# RCAuto.net
KiCad netlist of a schematic drawn in Altium Designer
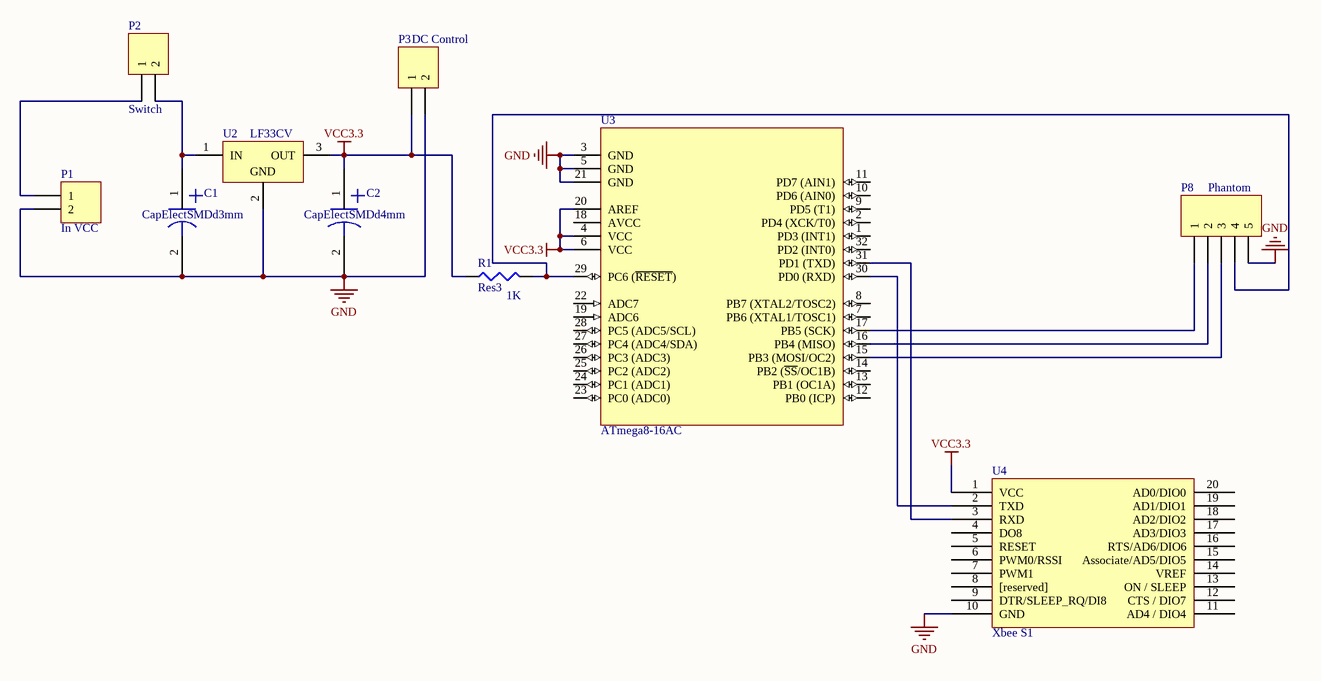
[diagram p0: RCAuto.SchDoc]

(export (version "E")
  (design (tool "Eeschema 10.0.6"))
  (components
    (comp (ref "C1")
      (value "CapElectSMDd3mm")
      (footprint "CapElectSMDd3mm")
      (libsource (lib "CapElectSMDd3mm") (part "CapElectSMDd3mm"))
    )
    (comp (ref "C2")
      (value "CapElectSMDd4mm")
      (footprint "CapElectSMDd4mm")
      (libsource (lib "CapElectSMDd4mm") (part "CapElectSMDd4mm"))
    )
    (comp (ref "P1")
      (value "In VCC")
      (footprint "HDR1X2")
      (description "Header, 2-Pin")
      (fields (field (name "PUBLISHER") "Altium Limited"))
      (libsource (lib "") (part "Header 2_1"))
    )
    (comp (ref "P2")
      (value "Switch")
      (footprint "HDR1X2")
      (description "Header, 2-Pin")
      (fields (field (name "PUBLISHER") "Altium Limited"))
      (libsource (lib "Miscellaneous Connectors") (part "Header 2"))
    )
    (comp (ref "P3")
      (value "DC Control")
      (footprint "HDR1X2")
      (description "Header, 2-Pin")
      (fields (field (name "PUBLISHER") "Altium Limited"))
      (libsource (lib "Miscellaneous Connectors") (part "Header 2"))
    )
    (comp (ref "P8")
      (value "Phantom")
      (footprint "HDR1X5")
      (description "Header, 5-Pin")
      (fields (field (name "PUBLISHER") "Altium Limited"))
      (libsource (lib "Miscellaneous Connectors") (part "Header 5"))
    )
    (comp (ref "R1")
      (value "Res3")
      (footprint "14-1206")
      (description "Resistor")
      (fields (field (name "ALTIUM_VALUE") "1K") (field (name "PUBLISHER") "Altium Limited"))
      (libsource (lib "Miscellaneous Devices") (part "Res3"))
    )
    (comp (ref "U2")
      (value "LF33CV")
      (footprint "TO-220A")
      (description "500mA, Very Low Drop (0.45V) Voltage Regulator")
      (fields (field (name "PUBLISHER") "Altium Limited"))
      (libsource (lib "ST Power Mgt Voltage Regulator") (part "LF33CV"))
    )
    (comp (ref "U3")
      (value "ATmega8-16AC")
      (footprint "32A_N")
      (description "8-Bit AVR Microcontroller with 8K Bytes of In-System Programmable Flash Memory")
      (fields (field (name "PUBLISHER") "Altium Limited"))
      (libsource (lib "Atmel Microcontroller 8-Bit AVR") (part "ATmega8-16AC"))
    )
    (comp (ref "U4") (value "Xbee S1") (footprint "Xbee S1") (libsource (lib "Xbee S1") (part "Xbee S1")))
  )
  (nets
    (net (code "1") (name "GND") (class "Default")
      (node (ref "C1") (pin "2") (pinfunction "2_2") (pintype "passive"))
      (node (ref "C2") (pin "2") (pinfunction "2_2") (pintype "passive"))
      (node (ref "P1") (pin "2") (pinfunction "2_2") (pintype "passive"))
      (node (ref "P3") (pin "2") (pinfunction "2_2") (pintype "passive"))
      (node (ref "P8") (pin "5") (pinfunction "5_5") (pintype "passive"))
      (node (ref "U2") (pin "2") (pinfunction "GND_2") (pintype "power_in"))
      (node (ref "U3") (pin "21") (pinfunction "GND_21") (pintype "power_in"))
      (node (ref "U3") (pin "3") (pinfunction "GND_3") (pintype "power_in"))
      (node (ref "U3") (pin "5") (pinfunction "GND_5") (pintype "power_in"))
      (node (ref "U4") (pin "10") (pinfunction "GND_10") (pintype "passive"))
    )
    (net (code "2") (name "Net-(P1-Pad1)") (class "Default")
      (node (ref "P1") (pin "1") (pinfunction "1_1") (pintype "passive"))
      (node (ref "P2") (pin "1") (pinfunction "1_1") (pintype "passive"))
    )
    (net (code "3") (name "Net-(U2-IN)") (class "Default")
      (node (ref "C1") (pin "1") (pinfunction "1_1") (pintype "passive"))
      (node (ref "P2") (pin "2") (pinfunction "2_2") (pintype "passive"))
      (node (ref "U2") (pin "1") (pinfunction "IN_1") (pintype "power_in"))
    )
    (net (code "4") (name "Net-(U3-PB3_(MOSI{slash}OC2))") (class "Default")
      (node (ref "P8") (pin "3") (pinfunction "3_3") (pintype "passive"))
      (node (ref "U3") (pin "15") (pinfunction "PB3_(MOSI/OC2)_15") (pintype "bidirectional"))
    )
    (net (code "5") (name "Net-(U3-PB4_(MISO))") (class "Default")
      (node (ref "P8") (pin "2") (pinfunction "2_2") (pintype "passive"))
      (node (ref "U3") (pin "16") (pinfunction "PB4_(MISO)_16") (pintype "bidirectional"))
    )
    (net (code "6") (name "Net-(U3-PB5_(SCK))") (class "Default")
      (node (ref "P8") (pin "1") (pinfunction "1_1") (pintype "passive"))
      (node (ref "U3") (pin "17") (pinfunction "PB5_(SCK)_17") (pintype "bidirectional"))
    )
    (net (code "7") (name "Net-(U3-PC6_(~{RESET}))") (class "Default")
      (node (ref "P8") (pin "4") (pinfunction "4_4") (pintype "passive"))
      (node (ref "R1") (pin "2") (pinfunction "2_2") (pintype "passive"))
      (node (ref "U3") (pin "29") (pinfunction "PC6_(~{RESET})_29") (pintype "bidirectional"))
    )
    (net (code "8") (name "Net-(U3-PD0_(RXD))") (class "Default")
      (node (ref "U3") (pin "30") (pinfunction "PD0_(RXD)_30") (pintype "bidirectional"))
      (node (ref "U4") (pin "2") (pinfunction "TXD_2") (pintype "passive"))
    )
    (net (code "9") (name "Net-(U3-PD1_(TXD))") (class "Default")
      (node (ref "U3") (pin "31") (pinfunction "PD1_(TXD)_31") (pintype "bidirectional"))
      (node (ref "U4") (pin "3") (pinfunction "RXD_3") (pintype "passive"))
    )
    (net (code "10") (name "VCC3.3") (class "Default")
      (node (ref "C2") (pin "1") (pinfunction "1_1") (pintype "passive"))
      (node (ref "P3") (pin "1") (pinfunction "1_1") (pintype "passive"))
      (node (ref "R1") (pin "1") (pinfunction "1_1") (pintype "passive"))
      (node (ref "U2") (pin "3") (pinfunction "OUT_3") (pintype "power_in"))
      (node (ref "U3") (pin "20") (pinfunction "AREF_20") (pintype "passive"))
      (node (ref "U3") (pin "4") (pinfunction "VCC_4") (pintype "power_in"))
      (node (ref "U3") (pin "6") (pinfunction "VCC_6") (pintype "power_in"))
      (node (ref "U4") (pin "1") (pinfunction "VCC_1") (pintype "passive"))
    )
    (net (code "11") (name "unconnected-(U3-ADC6-Pad19)") (class "Default")
      (node (ref "U3") (pin "19") (pinfunction "ADC6_19") (pintype "input"))
    )
    (net (code "12") (name "unconnected-(U3-ADC7-Pad22)") (class "Default")
      (node (ref "U3") (pin "22") (pinfunction "ADC7_22") (pintype "input"))
    )
    (net (code "13") (name "unconnected-(U3-AVCC-Pad18)") (class "Default")
      (node (ref "U3") (pin "18") (pinfunction "AVCC_18") (pintype "power_in"))
    )
    (net (code "14") (name "unconnected-(U3-PB0_(ICP)-Pad12)") (class "Default")
      (node (ref "U3") (pin "12") (pinfunction "PB0_(ICP)_12") (pintype "bidirectional"))
    )
    (net (code "15") (name "unconnected-(U3-PB1_(OC1A)-Pad13)") (class "Default")
      (node (ref "U3") (pin "13") (pinfunction "PB1_(OC1A)_13") (pintype "bidirectional"))
    )
    (net (code "16") (name "unconnected-(U3-PB2_(~{SS}{slash}OC1B)-Pad14)") (class "Default")
      (node (ref "U3") (pin "14") (pinfunction "PB2_(~{SS}/OC1B)_14") (pintype "bidirectional"))
    )
    (net (code "17") (name "unconnected-(U3-PB6_(XTAL1{slash}TOSC1)-Pad7)") (class "Default")
      (node (ref "U3") (pin "7") (pinfunction "PB6_(XTAL1/TOSC1)_7") (pintype "bidirectional"))
    )
    (net (code "18") (name "unconnected-(U3-PB7_(XTAL2{slash}TOSC2)-Pad8)") (class "Default")
      (node (ref "U3") (pin "8") (pinfunction "PB7_(XTAL2/TOSC2)_8") (pintype "bidirectional"))
    )
    (net (code "19") (name "unconnected-(U3-PC0_(ADC0)-Pad23)") (class "Default")
      (node (ref "U3") (pin "23") (pinfunction "PC0_(ADC0)_23") (pintype "bidirectional"))
    )
    (net (code "20") (name "unconnected-(U3-PC1_(ADC1)-Pad24)") (class "Default")
      (node (ref "U3") (pin "24") (pinfunction "PC1_(ADC1)_24") (pintype "bidirectional"))
    )
    (net (code "21") (name "unconnected-(U3-PC2_(ADC2)-Pad25)") (class "Default")
      (node (ref "U3") (pin "25") (pinfunction "PC2_(ADC2)_25") (pintype "bidirectional"))
    )
    (net (code "22") (name "unconnected-(U3-PC3_(ADC3)-Pad26)") (class "Default")
      (node (ref "U3") (pin "26") (pinfunction "PC3_(ADC3)_26") (pintype "bidirectional"))
    )
    (net (code "23") (name "unconnected-(U3-PC4_(ADC4{slash}SDA)-Pad27)") (class "Default")
      (node (ref "U3") (pin "27") (pinfunction "PC4_(ADC4/SDA)_27") (pintype "bidirectional"))
    )
    (net (code "24") (name "unconnected-(U3-PC5_(ADC5{slash}SCL)-Pad28)") (class "Default")
      (node (ref "U3") (pin "28") (pinfunction "PC5_(ADC5/SCL)_28") (pintype "bidirectional"))
    )
    (net (code "25") (name "unconnected-(U3-PD2_(INT0)-Pad32)") (class "Default")
      (node (ref "U3") (pin "32") (pinfunction "PD2_(INT0)_32") (pintype "bidirectional"))
    )
    (net (code "26") (name "unconnected-(U3-PD3_(INT1)-Pad1)") (class "Default")
      (node (ref "U3") (pin "1") (pinfunction "PD3_(INT1)_1") (pintype "bidirectional"))
    )
    (net (code "27") (name "unconnected-(U3-PD4_(XCK{slash}T0)-Pad2)") (class "Default")
      (node (ref "U3") (pin "2") (pinfunction "PD4_(XCK/T0)_2") (pintype "bidirectional"))
    )
    (net (code "28") (name "unconnected-(U3-PD5_(T1)-Pad9)") (class "Default")
      (node (ref "U3") (pin "9") (pinfunction "PD5_(T1)_9") (pintype "bidirectional"))
    )
    (net (code "29") (name "unconnected-(U3-PD6_(AIN0)-Pad10)") (class "Default")
      (node (ref "U3") (pin "10") (pinfunction "PD6_(AIN0)_10") (pintype "bidirectional"))
    )
    (net (code "30") (name "unconnected-(U3-PD7_(AIN1)-Pad11)") (class "Default")
      (node (ref "U3") (pin "11") (pinfunction "PD7_(AIN1)_11") (pintype "bidirectional"))
    )
    (net (code "31") (name "unconnected-(U4-AD0{slash}DIO0-Pad20)") (class "Default")
      (node (ref "U4") (pin "20") (pinfunction "AD0/DIO0_20") (pintype "passive"))
    )
    (net (code "32") (name "unconnected-(U4-AD1{slash}DIO1-Pad19)") (class "Default")
      (node (ref "U4") (pin "19") (pinfunction "AD1/DIO1_19") (pintype "passive"))
    )
    (net (code "33") (name "unconnected-(U4-AD2{slash}DIO2-Pad18)") (class "Default")
      (node (ref "U4") (pin "18") (pinfunction "AD2/DIO2_18") (pintype "passive"))
    )
    (net (code "34") (name "unconnected-(U4-AD3{slash}DIO3-Pad17)") (class "Default")
      (node (ref "U4") (pin "17") (pinfunction "AD3/DIO3_17") (pintype "passive"))
    )
    (net (code "35") (name "unconnected-(U4-AD4_{slash}_DIO4-Pad11)") (class "Default")
      (node (ref "U4") (pin "11") (pinfunction "AD4_/_DIO4_11") (pintype "passive"))
    )
    (net (code "36") (name "unconnected-(U4-Associate{slash}AD5{slash}DIO5-Pad15)") (class "Default")
      (node (ref "U4") (pin "15") (pinfunction "Associate/AD5/DIO5_15") (pintype "passive"))
    )
    (net (code "37") (name "unconnected-(U4-CTS_{slash}_DIO7-Pad12)") (class "Default")
      (node (ref "U4") (pin "12") (pinfunction "CTS_/_DIO7_12") (pintype "passive"))
    )
    (net (code "38") (name "unconnected-(U4-DO8-Pad4)") (class "Default")
      (node (ref "U4") (pin "4") (pinfunction "DO8_4") (pintype "passive"))
    )
    (net (code "39") (name "unconnected-(U4-DTR{slash}SLEEP_RQ{slash}DI8-Pad9)") (class "Default")
      (node (ref "U4") (pin "9") (pinfunction "DTR/SLEEP_RQ/DI8_9") (pintype "passive"))
    )
    (net (code "40") (name "unconnected-(U4-ON_{slash}_SLEEP-Pad13)") (class "Default")
      (node (ref "U4") (pin "13") (pinfunction "ON_/_SLEEP_13") (pintype "passive"))
    )
    (net (code "41") (name "unconnected-(U4-PWM0{slash}RSSI-Pad6)") (class "Default")
      (node (ref "U4") (pin "6") (pinfunction "PWM0/RSSI_6") (pintype "passive"))
    )
    (net (code "42") (name "unconnected-(U4-PWM1-Pad7)") (class "Default")
      (node (ref "U4") (pin "7") (pinfunction "PWM1_7") (pintype "passive"))
    )
    (net (code "43") (name "unconnected-(U4-RESET-Pad5)") (class "Default")
      (node (ref "U4") (pin "5") (pinfunction "RESET_5") (pintype "passive"))
    )
    (net (code "44") (name "unconnected-(U4-RTS{slash}AD6{slash}DIO6-Pad16)") (class "Default")
      (node (ref "U4") (pin "16") (pinfunction "RTS/AD6/DIO6_16") (pintype "passive"))
    )
    (net (code "45") (name "unconnected-(U4-VREF-Pad14)") (class "Default")
      (node (ref "U4") (pin "14") (pinfunction "VREF_14") (pintype "passive"))
    )
    (net (code "46") (name "unconnected-(U4-[reserved]-Pad8)") (class "Default")
      (node (ref "U4") (pin "8") (pinfunction "[reserved]_8") (pintype "passive"))
    )
  )
)
